# CATS-FAT-Overview.net
KiCad netlist of a schematic drawn in Altium Designer
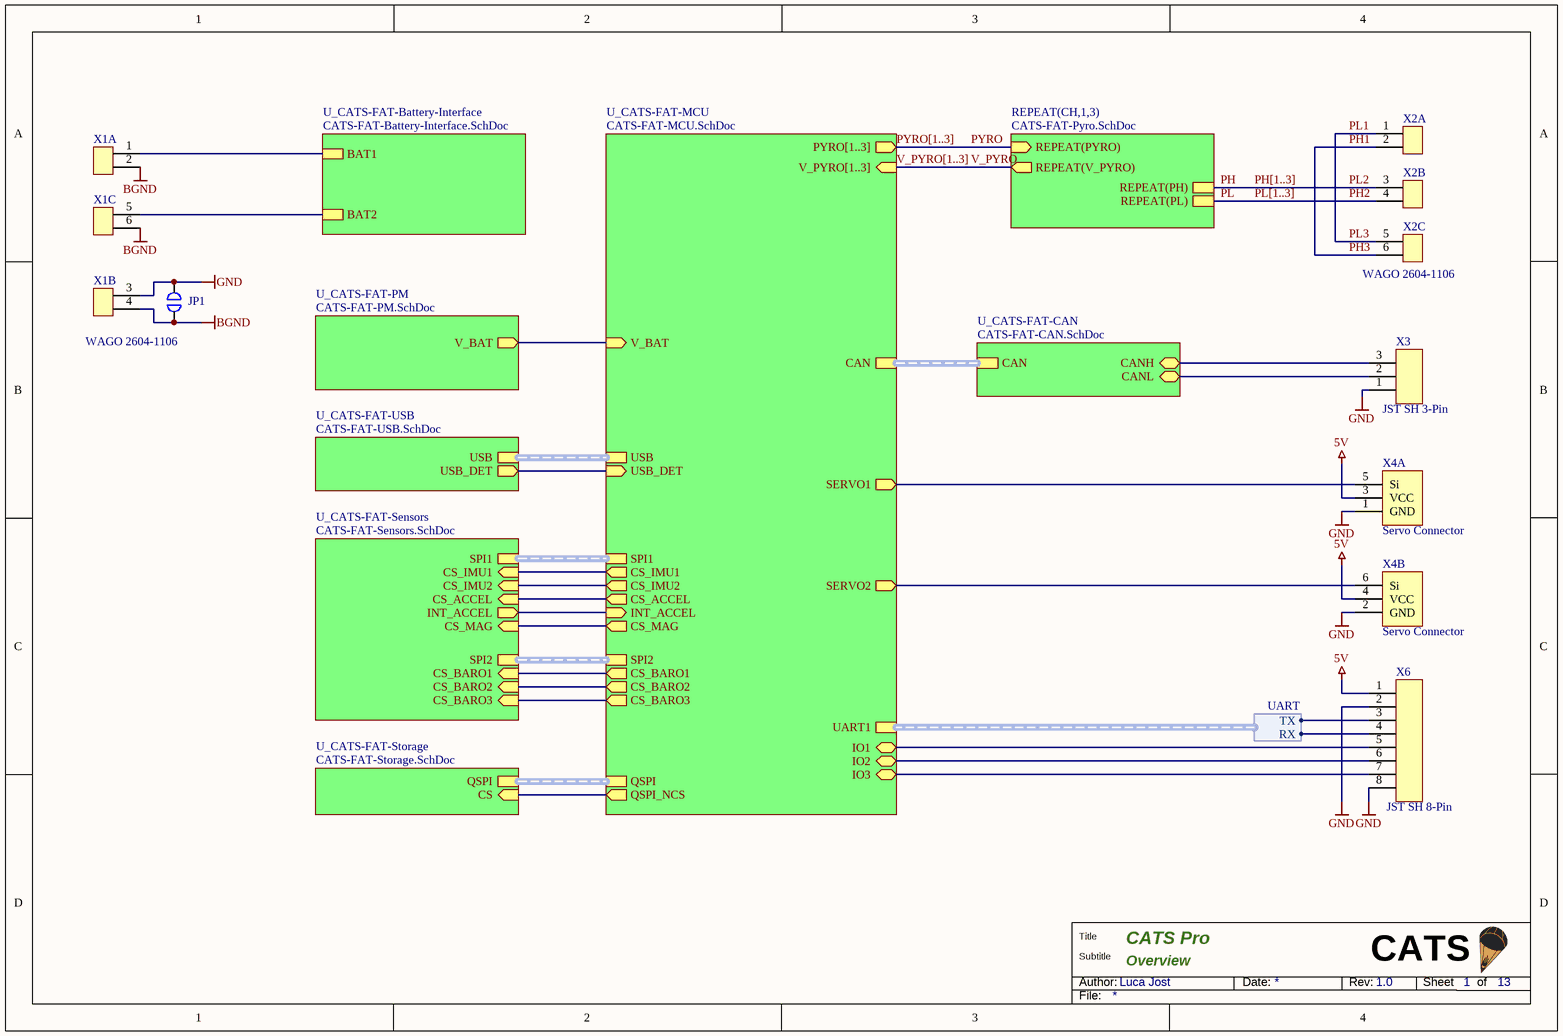
[diagram p0: CATS-FAT-Overview.SchDoc]

(export (version "E")
  (design (tool "Eeschema 10.0.6"))
  (components
    (comp (ref "JP1")
      (value "Jumper")
      (footprint "SMD Solder Jumper 1x2mm")
      (description "Single Position Jumper")
      (libsource (lib "Connectors") (part "Jumper-1"))
    )
    (comp (ref "X1")
      (value "WAGO 2604-1106")
      (footprint "THT PCB Terminal Wago 2604-1106")
      (description "PCB terminal blocks with levers and Push-in CAGE CLAMP® connection")
      (libsource (lib "Connectors") (part "WAGO 2604-1106"))
    )
    (comp (ref "X2")
      (value "WAGO 2604-1106")
      (footprint "THT PCB Terminal Wago 2604-1106")
      (description "PCB terminal blocks with levers and Push-in CAGE CLAMP® connection")
      (libsource (lib "") (part "WAGO 2604-1106_1"))
    )
    (comp (ref "X3")
      (value "JST SH 3-Pin")
      (footprint "SMD CONNECTOR JST-SR 3 PIN")
      (description "Crimp Style Connectors (Wire-to-Board type)")
      (libsource (lib "Connectors") (part "JST SH 3-Pin"))
    )
    (comp (ref "X4")
      (value "Servo Connector")
      (footprint "THT Stiftleiste 6-Pol (2x3) 90°")
      (description "6 Pin header for PWM servos")
      (libsource (lib "Connectors") (part "Servo Connector Dual"))
    )
    (comp (ref "X6")
      (value "JST SH 8-Pin")
      (footprint "SMD CONNECTOR JST-SR 8 PIN")
      (description "Crimp Style Connectors (Wire-to-Board type)")
      (libsource (lib "Connectors") (part "JST SH 8-Pin"))
    )
  )
  (nets
    (net (code "8") (name "/BAT1") (class "Default") (node (ref "X1") (pin "1") (pintype "passive")))
    (net (code "9") (name "/BAT2") (class "Default") (node (ref "X1") (pin "5") (pintype "passive")))
    (net (code "10") (name "/CANH") (class "Default")
      (node (ref "X3") (pin "3") (pinfunction "3_3") (pintype "passive"))
    )
    (net (code "11") (name "/CANL") (class "Default")
      (node (ref "X3") (pin "2") (pinfunction "2_2") (pintype "passive"))
    )
    (net (code "21") (name "/IO1") (class "Default")
      (node (ref "X6") (pin "5") (pinfunction "5_5") (pintype "passive"))
    )
    (net (code "22") (name "/IO2") (class "Default")
      (node (ref "X6") (pin "6") (pinfunction "6_6") (pintype "passive"))
    )
    (net (code "23") (name "/IO3") (class "Default")
      (node (ref "X6") (pin "7") (pinfunction "7_7") (pintype "passive"))
    )
    (net (code "25") (name "/PH1") (class "Default") (node (ref "X2") (pin "2") (pintype "passive")))
    (net (code "26") (name "/PH2") (class "Default") (node (ref "X2") (pin "4") (pintype "passive")))
    (net (code "27") (name "/PH3") (class "Default") (node (ref "X2") (pin "6") (pintype "passive")))
    (net (code "30") (name "/PL1") (class "Default") (node (ref "X2") (pin "1") (pintype "passive")))
    (net (code "31") (name "/PL2") (class "Default") (node (ref "X2") (pin "3") (pintype "passive")))
    (net (code "32") (name "/PL3") (class "Default") (node (ref "X2") (pin "5") (pintype "passive")))
    (net (code "38") (name "/RX") (class "Default")
      (node (ref "X6") (pin "4") (pinfunction "4_4") (pintype "passive"))
    )
    (net (code "39") (name "/SERVO1") (class "Default")
      (node (ref "X4") (pin "5") (pinfunction "Si_5") (pintype "passive"))
    )
    (net (code "40") (name "/SERVO2") (class "Default")
      (node (ref "X4") (pin "6") (pinfunction "Si_6") (pintype "passive"))
    )
    (net (code "43") (name "/TX") (class "Default")
      (node (ref "X6") (pin "3") (pinfunction "3_3") (pintype "passive"))
    )
    (net (code "50") (name "5V") (class "Default")
      (node (ref "X4") (pin "3") (pinfunction "VCC_3") (pintype "passive"))
      (node (ref "X4") (pin "4") (pinfunction "VCC_4") (pintype "passive"))
      (node (ref "X6") (pin "1") (pinfunction "1_1") (pintype "passive"))
    )
    (net (code "51") (name "BGND") (class "Default")
      (node (ref "JP1") (pin "2") (pintype "passive"))
      (node (ref "X1") (pin "2") (pintype "passive"))
      (node (ref "X1") (pin "4") (pintype "passive"))
      (node (ref "X1") (pin "6") (pintype "passive"))
    )
    (net (code "52") (name "GND") (class "Default")
      (node (ref "JP1") (pin "1") (pintype "passive"))
      (node (ref "X1") (pin "3") (pintype "passive"))
      (node (ref "X3") (pin "1") (pinfunction "1_1") (pintype "passive"))
      (node (ref "X4") (pin "1") (pinfunction "GND_1") (pintype "passive"))
      (node (ref "X4") (pin "2") (pinfunction "GND_2") (pintype "passive"))
      (node (ref "X6") (pin "2") (pinfunction "2_2") (pintype "passive"))
      (node (ref "X6") (pin "8") (pinfunction "8_8") (pintype "passive"))
    )
  )
)
